# voltagesumsource.net
KiCad netlist of a schematic drawn in Altium Designer
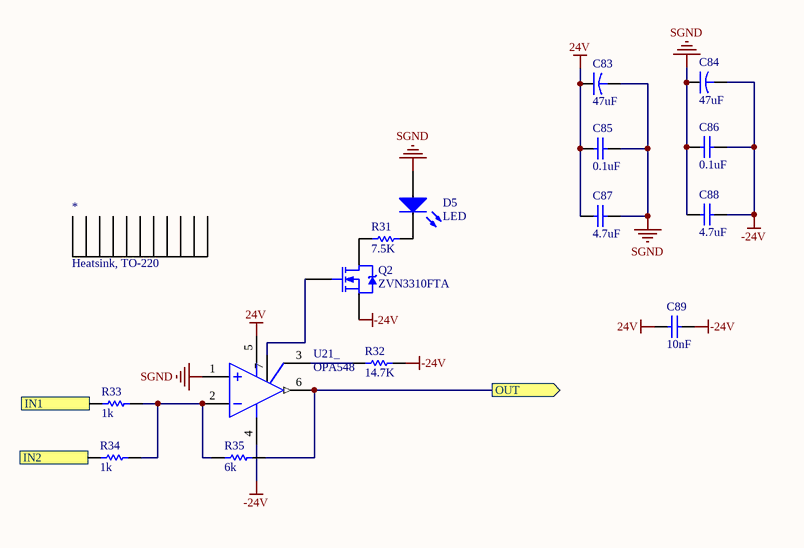
[diagram p0: voltagesumsource.SchDoc]

(export (version "E")
  (design (tool "Eeschema 10.0.6"))
  (components
    (comp (ref "*")
      (value "Heatsink, TO-220")
      (description "Heavy duty heatsink")
      (libsource (lib "Arturo_Approved") (part "6399BG"))
    )
    (comp (ref "C83")
      (value "47uF")
      (footprint "UCY2C470MPD")
      (description "Capacitor, 47uF NICHICON")
      (libsource (lib "Arturo_Approved") (part "UCY2C470MPD"))
    )
    (comp (ref "C84")
      (value "47uF")
      (footprint "UCY2C470MPD")
      (description "Capacitor, 47uF NICHICON")
      (libsource (lib "Arturo_Approved") (part "UCY2C470MPD"))
    )
    (comp (ref "C85")
      (value "0.1uF")
      (footprint "STD_0805_C")
      (description "Capacitor, 0.1uF, 0805")
      (libsource (lib "Arturo_Approved") (part "CL21B104KACNNNC"))
    )
    (comp (ref "C86")
      (value "0.1uF")
      (footprint "STD_0805_C")
      (description "Capacitor, 0.1uF, 0805")
      (libsource (lib "Arturo_Approved") (part "CL21B104KACNNNC"))
    )
    (comp (ref "C87")
      (value "4.7uF")
      (footprint "STD_0805_C")
      (description "Capacitor, 4.7uF, 0805")
      (libsource (lib "Arturo_Approved") (part "CL21A475KAQNNNE"))
    )
    (comp (ref "C88")
      (value "4.7uF")
      (footprint "STD_0805_C")
      (description "Capacitor, 4.7uF, 0805")
      (libsource (lib "Arturo_Approved") (part "CL21A475KAQNNNE"))
    )
    (comp (ref "C89")
      (value "10nF")
      (footprint "STD_0805_C")
      (description "Capacitor, 10nF, 0805")
      (libsource (lib "Arturo_Approved") (part "C0805C103K1RAC7210"))
    )
    (comp (ref "D5")
      (value "LED")
      (footprint "STD_LED")
      (description "Typical LED")
      (libsource (lib "Arturo_Approved") (part "LNJ037X8ARA"))
    )
    (comp (ref "Q2")
      (value "ZVN3310FTA")
      (footprint "SOT-23B_M")
      (description "N-Channel Power MOSFET")
      (libsource (lib "Arturo_Approved") (part "ZVN3310FTA"))
    )
    (comp (ref "R31")
      (value "7.5K")
      (footprint "STD_0805_R")
      (description "7.5K 1% 1/4W")
      (libsource (lib "Arturo_Approved") (part "ERJ-PB6D7501V"))
    )
    (comp (ref "R32")
      (value "14.7K")
      (footprint "STD_0805_R")
      (description "14.7K 1% 1/4W")
      (libsource (lib "Arturo_Approved") (part "RC0805FR-0714K7L"))
    )
    (comp (ref "R33")
      (value "1k")
      (footprint "STD_0805_R")
      (description "1K 1% 1/4W")
      (libsource (lib "Arturo_Approved") (part "RNCP0805FTD1K00"))
    )
    (comp (ref "R34")
      (value "1k")
      (footprint "STD_0805_R")
      (description "1K 1% 1/4W")
      (libsource (lib "Arturo_Approved") (part "RNCP0805FTD1K00"))
    )
    (comp (ref "R35")
      (value "6k")
      (footprint "STD_0805_R")
      (description "6K 1% 1/4W")
      (libsource (lib "Arturo_Approved") (part "RMCF0805FT5K60"))
    )
    (comp (ref "U21_")
      (value "OPA548")
      (footprint "TO-220-7")
      (description "High power op amp")
      (libsource (lib "Arturo_Approved") (part "OPA548T"))
    )
  )
  (nets
    (net (code "1") (name "-24V") (class "Default")
      (node (ref "C84") (pin "2") (pinfunction "2_2") (pintype "passive"))
      (node (ref "C86") (pin "2") (pinfunction "2_2") (pintype "passive"))
      (node (ref "C88") (pin "2") (pinfunction "2_2") (pintype "passive"))
      (node (ref "C89") (pin "2") (pinfunction "2_2") (pintype "passive"))
      (node (ref "Q2") (pin "3") (pinfunction "S_3") (pintype "passive"))
      (node (ref "R32") (pin "2") (pinfunction "2_2") (pintype "passive"))
      (node (ref "U21_") (pin "4") (pinfunction "V-_4") (pintype "power_in"))
    )
    (net (code "2") (name "/IN1") (class "Default")
      (node (ref "R33") (pin "1") (pinfunction "1_1") (pintype "passive"))
    )
    (net (code "3") (name "/IN2") (class "Default")
      (node (ref "R34") (pin "1") (pinfunction "1_1") (pintype "passive"))
    )
    (net (code "4") (name "/OUT") (class "Default")
      (node (ref "R35") (pin "2") (pinfunction "2_2") (pintype "passive"))
      (node (ref "U21_") (pin "6") (pinfunction "OUT_6") (pintype "output"))
    )
    (net (code "5") (name "24V") (class "Default")
      (node (ref "C83") (pin "1") (pinfunction "1_1") (pintype "passive"))
      (node (ref "C85") (pin "1") (pinfunction "1_1") (pintype "passive"))
      (node (ref "C87") (pin "1") (pinfunction "1_1") (pintype "passive"))
      (node (ref "C89") (pin "1") (pinfunction "1_1") (pintype "passive"))
      (node (ref "U21_") (pin "5") (pinfunction "V+_5") (pintype "power_in"))
    )
    (net (code "6") (name "Net-(D5-Pad2)") (class "Default")
      (node (ref "D5") (pin "2") (pinfunction "2_2") (pintype "passive"))
      (node (ref "R31") (pin "2") (pinfunction "2_2") (pintype "passive"))
    )
    (net (code "7") (name "Net-(Q2-D)") (class "Default")
      (node (ref "Q2") (pin "2") (pinfunction "D_2") (pintype "passive"))
      (node (ref "R31") (pin "1") (pinfunction "1_1") (pintype "passive"))
    )
    (net (code "8") (name "Net-(Q2-G)") (class "Default")
      (node (ref "Q2") (pin "1") (pinfunction "G_1") (pintype "passive"))
      (node (ref "U21_") (pin "7") (pinfunction "OS_NUL_7") (pintype "passive"))
    )
    (net (code "9") (name "Net-(U21_-IN+)") (class "Default")
      (node (ref "R33") (pin "2") (pinfunction "2_2") (pintype "passive"))
      (node (ref "R34") (pin "2") (pinfunction "2_2") (pintype "passive"))
      (node (ref "R35") (pin "1") (pinfunction "1_1") (pintype "passive"))
      (node (ref "U21_") (pin "2") (pinfunction "IN+_2") (pintype "passive"))
    )
    (net (code "10") (name "Net-(U21_-TAB)") (class "Default")
      (node (ref "R32") (pin "1") (pinfunction "1_1") (pintype "passive"))
      (node (ref "U21_") (pin "3") (pinfunction "TAB_3") (pintype "passive"))
    )
    (net (code "11") (name "SGND") (class "Default")
      (node (ref "C83") (pin "2") (pinfunction "2_2") (pintype "passive"))
      (node (ref "C84") (pin "1") (pinfunction "1_1") (pintype "passive"))
      (node (ref "C85") (pin "2") (pinfunction "2_2") (pintype "passive"))
      (node (ref "C86") (pin "1") (pinfunction "1_1") (pintype "passive"))
      (node (ref "C87") (pin "2") (pinfunction "2_2") (pintype "passive"))
      (node (ref "C88") (pin "1") (pinfunction "1_1") (pintype "passive"))
      (node (ref "D5") (pin "1") (pinfunction "1_1") (pintype "passive"))
      (node (ref "U21_") (pin "1") (pinfunction "IN-_1") (pintype "passive"))
    )
  )
)
